# SENSORS_FMU3_REV_C.net
KiCad netlist of a schematic drawn in Altium Designer
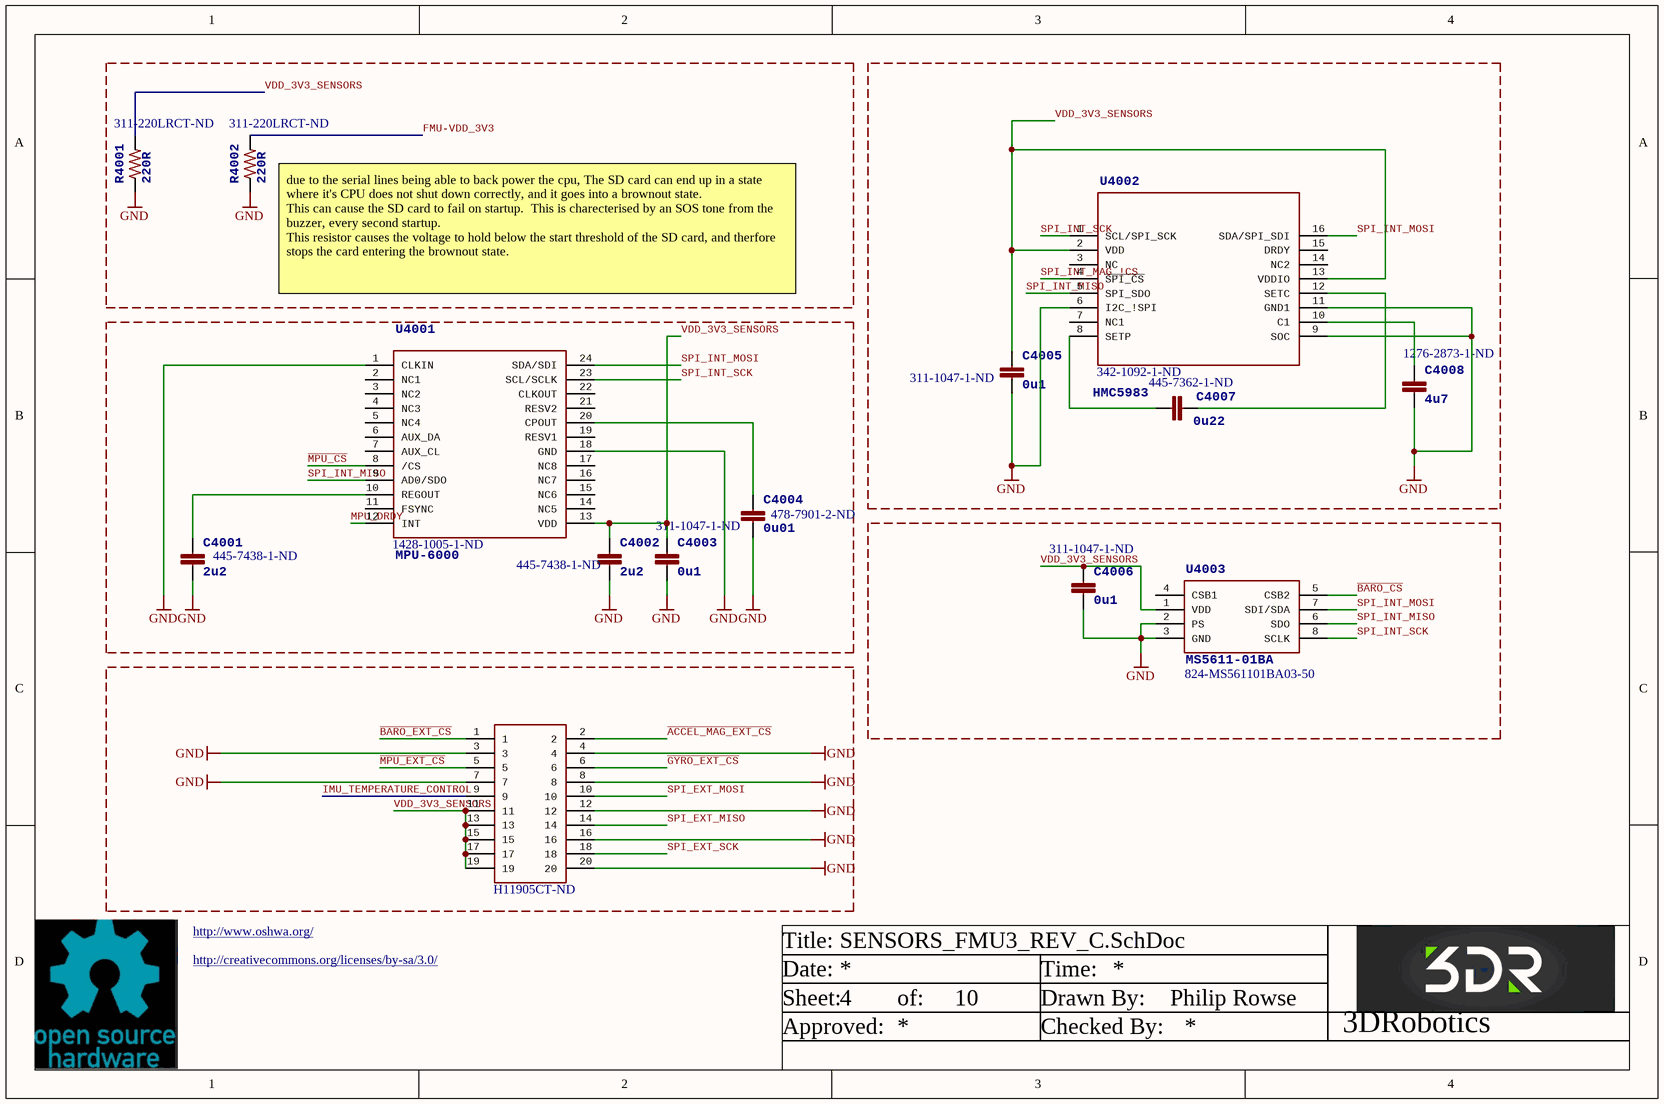
[diagram p0: SENSORS_FMU3_REV_C.SchDoc]

(export (version "E")
  (design (tool "Eeschema 10.0.6"))
  (components
    (comp (ref "C4001")
      (value "2u2")
      (footprint "0603-CAP")
      (description "CAP CER 2.2UF 16V 10% X6S 0603")
      (fields
        (field (name "PARTNO") "C1608X6S1C225K080AC")
        (field (name "SUPPLIER PART NUMBER 1") "445-7438-1-ND")
        (field (name "3DR_PARTNO") "ECM0619")
      )
      (libsource (lib "pixhawk2") (part "CAP0603"))
    )
    (comp (ref "C4002")
      (value "2u2")
      (footprint "0603-CAP")
      (description "CAP CER 2.2UF 16V 10% X6S 0603")
      (fields
        (field (name "PARTNO") "C1608X6S1C225K080AC")
        (field (name "SUPPLIER PART NUMBER 1") "445-7438-1-ND")
        (field (name "3DR_PARTNO") "ECM0619")
      )
      (libsource (lib "pixhawk2") (part "CAP0603"))
    )
    (comp (ref "C4003")
      (value "0u1")
      (footprint "0402-CAP")
      (description "CAP CER 0.1UF 16V Y5V 0402")
      (fields
        (field (name "PARTNO") "CC0402ZRY5V7BB104")
        (field (name "SUPPLIER PART NUMBER 1") "311-1047-1-ND")
        (field (name "3DR_PARTNO") "ECM0700")
      )
      (libsource (lib "pixhawk2") (part "CAP0402"))
    )
    (comp (ref "C4004")
      (value "0u01")
      (footprint "0603-CAP")
      (description "CAP CER 10000PF 25V 5% X7R 0603")
      (fields
        (field (name "PARTNO") "06033C103JAT2A")
        (field (name "SUPPLIER PART NUMBER 1") "478-7901-2-ND")
        (field (name "3DR_PARTNO") "ECM0620")
      )
      (libsource (lib "pixhawk2") (part "CAP0603"))
    )
    (comp (ref "C4005")
      (value "0u1")
      (footprint "0402-CAP")
      (description "CAP CER 0.1UF 16V Y5V 0402")
      (fields
        (field (name "SUPPLIER PART NUMBER 1") "311-1047-1-ND")
        (field (name "3DR_PARTNO") "ECM0700")
        (field (name "PARTNO") "CC0402ZRY5V7BB104")
      )
      (libsource (lib "pixhawk2") (part "CAP0402"))
    )
    (comp (ref "C4006")
      (value "0u1")
      (footprint "0402-CAP")
      (description "CAP CER 0.1UF 16V Y5V 0402")
      (fields
        (field (name "PARTNO") "CC0402ZRY5V7BB104")
        (field (name "SUPPLIER PART NUMBER 1") "311-1047-1-ND")
        (field (name "3DR_PARTNO") "ECM0700")
      )
      (libsource (lib "pixhawk2") (part "CAP0402"))
    )
    (comp (ref "C4007")
      (value "0u22")
      (footprint "0402-CAP")
      (description "CAP CER 0.22UF 25V 10% X7R 0402")
      (fields
        (field (name "3DR_PARTNO") "ECM")
        (field (name "PARTNO") "C1005X6S1E224K050BC")
        (field (name "SUPPLIER PART NUMBER 1") "445-7362-1-ND")
      )
      (libsource (lib "") (part "CAP0402_1"))
    )
    (comp (ref "C4008")
      (value "4u7")
      (footprint "0805")
      (description "CAP CER 4.7UF 16V 10% X7R 0805")
      (fields
        (field (name "PARTNO") "CL21B475KOFNNNE")
        (field (name "SUPPLIER PART NUMBER 1") "1276-2873-1-ND")
        (field (name "3DR_PARTNO") "ECM0622")
      )
      (libsource (lib "pixhawk2") (part "CAP0805"))
    )
    (comp (ref "R4001")
      (value "220R")
      (footprint "0402-RES")
      (description "RES 220 OHM 1/16W 1% 0402 SMD")
      (fields
        (field (name "SUPPLIER PART NUMBER 1") "311-220LRCT-ND")
        (field (name "3DR_PARTNO") "ECM0821")
        (field (name "PARTNO") "RC0402FR-07220RL")
      )
      (libsource (lib "pixhawk2") (part "RESISTOR0402-RES"))
    )
    (comp (ref "R4002")
      (value "220R")
      (footprint "0402-RES")
      (description "RES 220 OHM 1/16W 1% 0402 SMD")
      (fields
        (field (name "SUPPLIER PART NUMBER 1") "311-220LRCT-ND")
        (field (name "3DR_PARTNO") "ECM0821")
        (field (name "PARTNO") "RC0402FR-07220RL")
      )
      (libsource (lib "pixhawk2") (part "RESISTOR0402-RES"))
    )
    (comp (ref "U$2")
      (value "DF40C-20-DS")
      (footprint "DF-40C-20DS")
      (description "CONN RCPT 20POS 0.4MM SMD GOLD")
      (fields
        (field (name "SUPPLIER PART NUMBER 1") "H11905CT-ND")
        (field (name "3DR_PARTNO") "ECM0517")
        (field (name "PARTNO") "DF40C(2.0)-20DS-0.4V(51)")
      )
      (libsource (lib "pixhawk2") (part "DF40C-20-DS"))
    )
    (comp (ref "U4001")
      (value "MPU-6000")
      (footprint "QFN-24")
      (description "GYRO/ACCELEROMETER 6AXIS 24QFN")
      (fields (field (name "SUPPLIER PART NUMBER 1") "1428-1005-1-ND") (field (name "3DR_PARTNO") "ECM0834"))
      (libsource (lib "pixhawk2") (part "MPU-6000"))
    )
    (comp (ref "U4002")
      (value "HMC5983")
      (footprint "HMC5983-new")
      (description "IC COMPASS 3 AXIS 16-LCC")
      (fields (field (name "SUPPLIER PART NUMBER 1") "342-1092-1-ND") (field (name "3DR_PARTNO") "ECM0672"))
      (libsource (lib "pixhawk2") (part "HMC5983"))
    )
    (comp (ref "U4003")
      (value "MS5611-01BA")
      (footprint "MS5611-01BA")
      (description "Board Mount Pressure Sensors")
      (fields
        (field (name "SUPPLIER PART NUMBER 1") "824-MS561101BA03-50")
        (field (name "3DR_PARTNO") "ECM0835")
      )
      (libsource (lib "pixhawk2") (part "MS5611-01BA"))
    )
  )
  (nets
    (net (code "1") (name "/FMU-VDD_3V3") (class "Default")
      (node (ref "R4002") (pin "P$2") (pinfunction "2_P$2") (pintype "passive"))
    )
    (net (code "2") (name "/IMU_TEMPERATURE_CONTROL") (class "Default")
      (node (ref "U$2") (pin "9") (pinfunction "9_9") (pintype "passive"))
    )
    (net (code "3") (name "/MPU_DRDY") (class "Default")
      (node (ref "U4001") (pin "12") (pinfunction "INT_12") (pintype "passive"))
    )
    (net (code "4") (name "/SPI_EXT_MISO") (class "Default")
      (node (ref "U$2") (pin "14") (pinfunction "14_14") (pintype "passive"))
    )
    (net (code "5") (name "/SPI_EXT_MOSI") (class "Default")
      (node (ref "U$2") (pin "10") (pinfunction "10_10") (pintype "passive"))
    )
    (net (code "6") (name "/SPI_EXT_SCK") (class "Default")
      (node (ref "U$2") (pin "18") (pinfunction "18_18") (pintype "passive"))
    )
    (net (code "7") (name "/SPI_INT_MAG_!CS") (class "Default")
      (node (ref "U4002") (pin "4") (pinfunction "~{SPI_CS}_4") (pintype "passive"))
    )
    (net (code "8") (name "/SPI_INT_MISO") (class "Default")
      (node (ref "U4001") (pin "9") (pinfunction "AD0/SDO_9") (pintype "passive"))
      (node (ref "U4002") (pin "5") (pinfunction "SPI_SDO_5") (pintype "passive"))
      (node (ref "U4003") (pin "6") (pinfunction "SDO_6") (pintype "passive"))
    )
    (net (code "9") (name "/SPI_INT_MOSI") (class "Default")
      (node (ref "U4001") (pin "24") (pinfunction "SDA/SDI_24") (pintype "passive"))
      (node (ref "U4002") (pin "16") (pinfunction "SDA/SPI_SDI_16") (pintype "passive"))
      (node (ref "U4003") (pin "7") (pinfunction "SDI/SDA_7") (pintype "passive"))
    )
    (net (code "10") (name "/SPI_INT_SCK") (class "Default")
      (node (ref "U4001") (pin "23") (pinfunction "SCL/SCLK_23") (pintype "passive"))
      (node (ref "U4002") (pin "1") (pinfunction "SCL/SPI_SCK_1") (pintype "passive"))
      (node (ref "U4003") (pin "8") (pinfunction "SCLK_8") (pintype "passive"))
    )
    (net (code "11") (name "/VDD_3V3_SENSORS") (class "Default")
      (node (ref "C4002") (pin "P$1") (pinfunction "1_P$1") (pintype "passive"))
      (node (ref "C4003") (pin "P$1") (pinfunction "1_P$1") (pintype "passive"))
      (node (ref "C4005") (pin "P$1") (pinfunction "1_P$1") (pintype "passive"))
      (node (ref "C4006") (pin "P$1") (pinfunction "1_P$1") (pintype "passive"))
      (node (ref "R4001") (pin "P$2") (pinfunction "2_P$2") (pintype "passive"))
      (node (ref "U$2") (pin "11") (pinfunction "11_11") (pintype "passive"))
      (node (ref "U$2") (pin "13") (pinfunction "13_13") (pintype "passive"))
      (node (ref "U$2") (pin "15") (pinfunction "15_15") (pintype "passive"))
      (node (ref "U$2") (pin "17") (pinfunction "17_17") (pintype "passive"))
      (node (ref "U$2") (pin "19") (pinfunction "19_19") (pintype "passive"))
      (node (ref "U4001") (pin "13") (pinfunction "VDD_13") (pintype "passive"))
      (node (ref "U4002") (pin "13") (pinfunction "VDDIO_13") (pintype "power_in"))
      (node (ref "U4002") (pin "2") (pinfunction "VDD_2") (pintype "power_in"))
      (node (ref "U4003") (pin "1") (pinfunction "VDD_1") (pintype "passive"))
    )
    (net (code "12") (name "/~{ACCEL_MAG_EXT_CS}") (class "Default")
      (node (ref "U$2") (pin "2") (pinfunction "2_2") (pintype "passive"))
    )
    (net (code "13") (name "/~{BARO_CS}") (class "Default")
      (node (ref "U4003") (pin "5") (pinfunction "CSB2_5") (pintype "passive"))
    )
    (net (code "14") (name "/~{BARO_EXT_CS}") (class "Default")
      (node (ref "U$2") (pin "1") (pinfunction "1_1") (pintype "passive"))
    )
    (net (code "15") (name "/~{GYRO_EXT_CS}") (class "Default")
      (node (ref "U$2") (pin "6") (pinfunction "6_6") (pintype "passive"))
    )
    (net (code "16") (name "/~{MPU_CS}") (class "Default")
      (node (ref "U4001") (pin "8") (pinfunction "/CS_8") (pintype "passive"))
    )
    (net (code "17") (name "/~{MPU_EXT_CS}") (class "Default")
      (node (ref "U$2") (pin "5") (pinfunction "5_5") (pintype "passive"))
    )
    (net (code "18") (name "GND") (class "Default")
      (node (ref "C4001") (pin "P$2") (pinfunction "2_P$2") (pintype "passive"))
      (node (ref "C4002") (pin "P$2") (pinfunction "2_P$2") (pintype "passive"))
      (node (ref "C4003") (pin "P$2") (pinfunction "2_P$2") (pintype "passive"))
      (node (ref "C4004") (pin "P$2") (pinfunction "2_P$2") (pintype "passive"))
      (node (ref "C4005") (pin "P$2") (pinfunction "2_P$2") (pintype "passive"))
      (node (ref "C4006") (pin "P$2") (pinfunction "2_P$2") (pintype "passive"))
      (node (ref "C4008") (pin "2") (pinfunction "2_2") (pintype "passive"))
      (node (ref "R4001") (pin "P$1") (pinfunction "1_P$1") (pintype "passive"))
      (node (ref "R4002") (pin "P$1") (pinfunction "1_P$1") (pintype "passive"))
      (node (ref "U$2") (pin "12") (pinfunction "12_12") (pintype "passive"))
      (node (ref "U$2") (pin "16") (pinfunction "16_16") (pintype "passive"))
      (node (ref "U$2") (pin "20") (pinfunction "20_20") (pintype "passive"))
      (node (ref "U$2") (pin "3") (pinfunction "3_3") (pintype "passive"))
      (node (ref "U$2") (pin "4") (pinfunction "4_4") (pintype "passive"))
      (node (ref "U$2") (pin "7") (pinfunction "7_7") (pintype "passive"))
      (node (ref "U$2") (pin "8") (pinfunction "8_8") (pintype "passive"))
      (node (ref "U4001") (pin "1") (pinfunction "CLKIN_1") (pintype "passive"))
      (node (ref "U4001") (pin "18") (pinfunction "GND_18") (pintype "passive"))
      (node (ref "U4002") (pin "11") (pinfunction "GND1_11") (pintype "passive"))
      (node (ref "U4002") (pin "6") (pinfunction "I2C_!SPI_6") (pintype "passive"))
      (node (ref "U4002") (pin "9") (pinfunction "SOC_9") (pintype "passive"))
      (node (ref "U4003") (pin "2") (pinfunction "PS_2") (pintype "passive"))
      (node (ref "U4003") (pin "3") (pinfunction "GND_3") (pintype "passive"))
    )
    (net (code "19") (name "Net-(C4001-1)") (class "Default")
      (node (ref "C4001") (pin "P$1") (pinfunction "1_P$1") (pintype "passive"))
      (node (ref "U4001") (pin "10") (pinfunction "REGOUT_10") (pintype "passive"))
    )
    (net (code "20") (name "Net-(C4004-1)") (class "Default")
      (node (ref "C4004") (pin "P$1") (pinfunction "1_P$1") (pintype "passive"))
      (node (ref "U4001") (pin "20") (pinfunction "CPOUT_20") (pintype "passive"))
    )
    (net (code "21") (name "Net-(C4007-1)") (class "Default")
      (node (ref "C4007") (pin "P$1") (pinfunction "1_P$1") (pintype "passive"))
      (node (ref "U4002") (pin "12") (pinfunction "SETC_12") (pintype "passive"))
    )
    (net (code "22") (name "Net-(C4007-2)") (class "Default")
      (node (ref "C4007") (pin "P$2") (pinfunction "2_P$2") (pintype "passive"))
      (node (ref "U4002") (pin "8") (pinfunction "SETP_8") (pintype "passive"))
    )
    (net (code "23") (name "Net-(U4002-C1)") (class "Default")
      (node (ref "C4008") (pin "1") (pinfunction "1_1") (pintype "passive"))
      (node (ref "U4002") (pin "10") (pinfunction "C1_10") (pintype "passive"))
    )
    (net (code "24") (name "unconnected-(U4001-AUX_CL-Pad7)") (class "Default")
      (node (ref "U4001") (pin "7") (pinfunction "AUX_CL_7") (pintype "passive"))
    )
    (net (code "25") (name "unconnected-(U4001-AUX_DA-Pad6)") (class "Default")
      (node (ref "U4001") (pin "6") (pinfunction "AUX_DA_6") (pintype "passive"))
    )
    (net (code "26") (name "unconnected-(U4001-CLKOUT-Pad22)") (class "Default")
      (node (ref "U4001") (pin "22") (pinfunction "CLKOUT_22") (pintype "passive"))
    )
    (net (code "27") (name "unconnected-(U4001-FSYNC-Pad11)") (class "Default")
      (node (ref "U4001") (pin "11") (pinfunction "FSYNC_11") (pintype "passive"))
    )
    (net (code "28") (name "unconnected-(U4001-NC1-Pad2)") (class "Default")
      (node (ref "U4001") (pin "2") (pinfunction "NC1_2") (pintype "passive"))
    )
    (net (code "29") (name "unconnected-(U4001-NC2-Pad3)") (class "Default")
      (node (ref "U4001") (pin "3") (pinfunction "NC2_3") (pintype "passive"))
    )
    (net (code "30") (name "unconnected-(U4001-NC3-Pad4)") (class "Default")
      (node (ref "U4001") (pin "4") (pinfunction "NC3_4") (pintype "passive"))
    )
    (net (code "31") (name "unconnected-(U4001-NC4-Pad5)") (class "Default")
      (node (ref "U4001") (pin "5") (pinfunction "NC4_5") (pintype "passive"))
    )
    (net (code "32") (name "unconnected-(U4001-NC5-Pad14)") (class "Default")
      (node (ref "U4001") (pin "14") (pinfunction "NC5_14") (pintype "passive"))
    )
    (net (code "33") (name "unconnected-(U4001-NC6-Pad15)") (class "Default")
      (node (ref "U4001") (pin "15") (pinfunction "NC6_15") (pintype "passive"))
    )
    (net (code "34") (name "unconnected-(U4001-NC7-Pad16)") (class "Default")
      (node (ref "U4001") (pin "16") (pinfunction "NC7_16") (pintype "passive"))
    )
    (net (code "35") (name "unconnected-(U4001-NC8-Pad17)") (class "Default")
      (node (ref "U4001") (pin "17") (pinfunction "NC8_17") (pintype "passive"))
    )
    (net (code "36") (name "unconnected-(U4001-RESV1-Pad19)") (class "Default")
      (node (ref "U4001") (pin "19") (pinfunction "RESV1_19") (pintype "passive"))
    )
    (net (code "37") (name "unconnected-(U4001-RESV2-Pad21)") (class "Default")
      (node (ref "U4001") (pin "21") (pinfunction "RESV2_21") (pintype "passive"))
    )
    (net (code "38") (name "unconnected-(U4002-DRDY-Pad15)") (class "Default")
      (node (ref "U4002") (pin "15") (pinfunction "DRDY_15") (pintype "passive"))
    )
    (net (code "39") (name "unconnected-(U4002-NC-Pad3)") (class "Default")
      (node (ref "U4002") (pin "3") (pinfunction "NC_3") (pintype "passive"))
    )
    (net (code "40") (name "unconnected-(U4002-NC1-Pad7)") (class "Default")
      (node (ref "U4002") (pin "7") (pinfunction "NC1_7") (pintype "passive"))
    )
    (net (code "41") (name "unconnected-(U4002-NC2-Pad14)") (class "Default")
      (node (ref "U4002") (pin "14") (pinfunction "NC2_14") (pintype "passive"))
    )
    (net (code "42") (name "unconnected-(U4003-CSB1-Pad4)") (class "Default")
      (node (ref "U4003") (pin "4") (pinfunction "CSB1_4") (pintype "passive"))
    )
  )
)
